# Boost_converter.net
KiCad netlist of a schematic drawn in Altium Designer
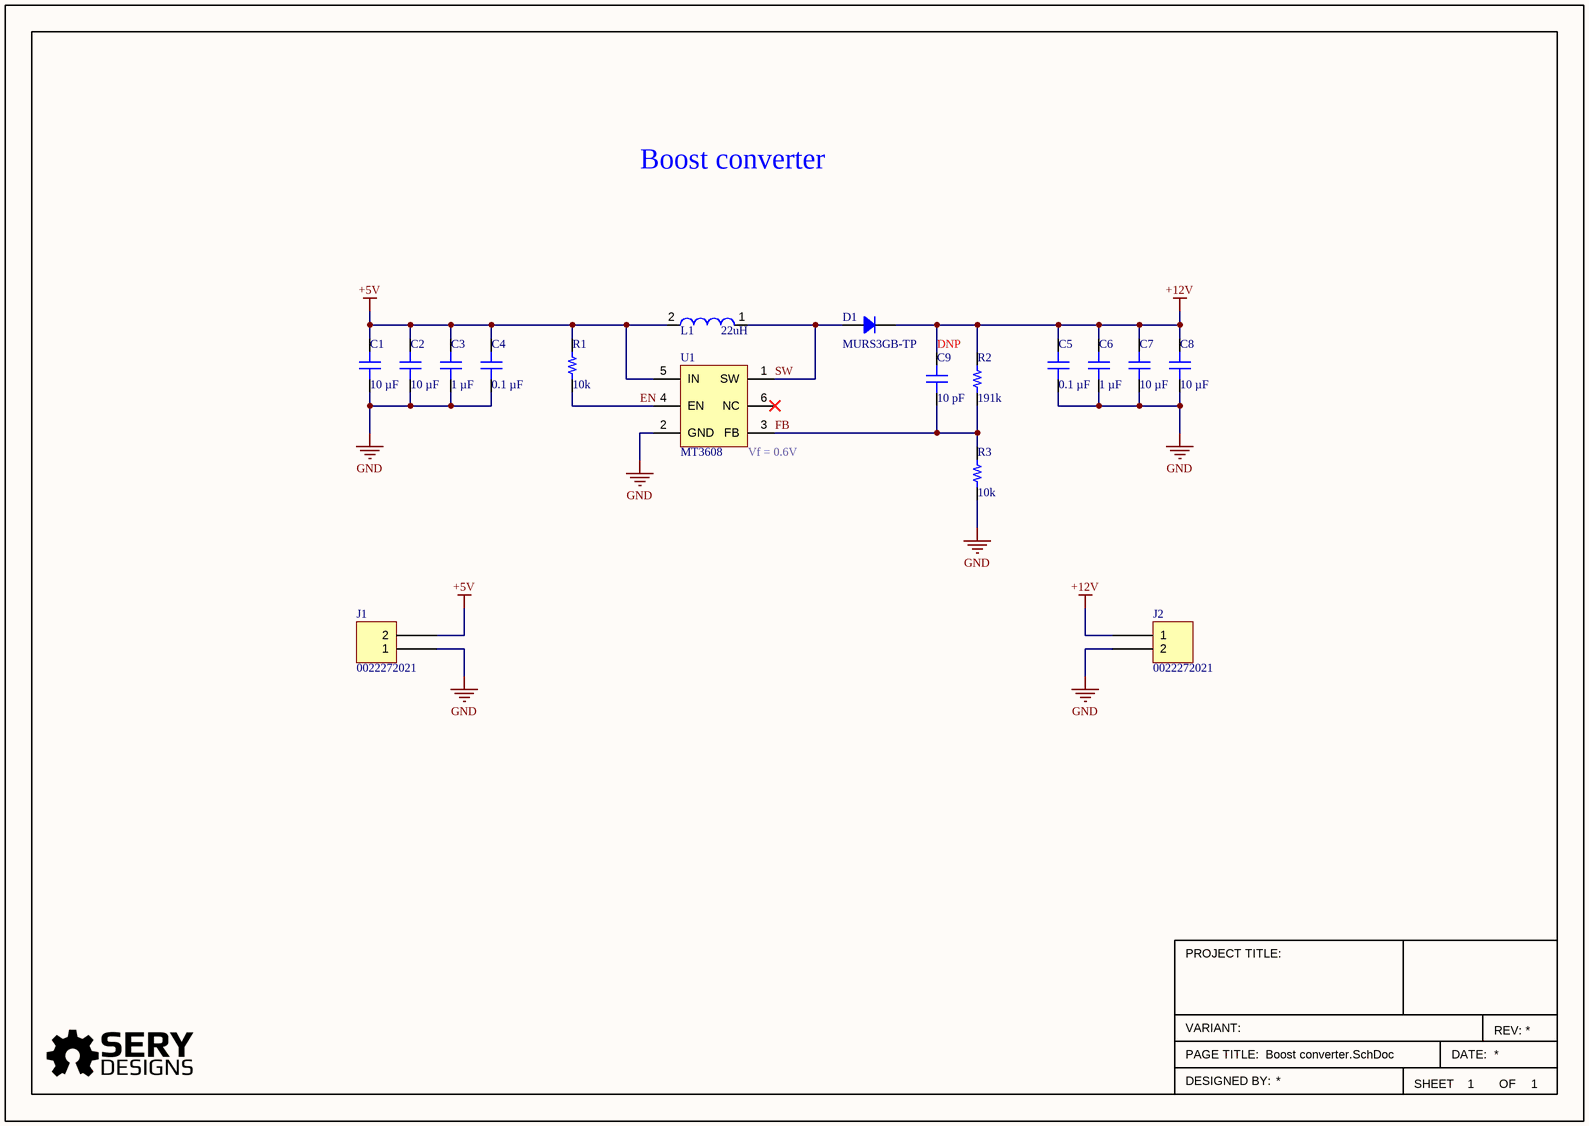
[diagram p0: Boost converter.SchDoc]

(export (version "E")
  (design (tool "Eeschema 10.0.6"))
  (components
    (comp (ref "C1")
      (value "10 µF")
      (footprint "CAP 0805_2012")
      (description "CAP CER 10UF 50V X5R 0805")
      (fields
        (field (name "PART NUMBER") "GRM21BR61H106ME43L")
        (field (name "MANUFACTURER") "Murata Electronics")
      )
      (libsource (lib "Celestial Altium Library - altium_library") (part "Capacitor"))
    )
    (comp (ref "C2")
      (value "10 µF")
      (footprint "CAP 0805_2012")
      (description "CAP CER 10UF 50V X5R 0805")
      (fields
        (field (name "PART NUMBER") "GRM21BR61H106ME43L")
        (field (name "MANUFACTURER") "Murata Electronics")
      )
      (libsource (lib "Celestial Altium Library - altium_library") (part "Capacitor"))
    )
    (comp (ref "C3")
      (value "1 µF")
      (footprint "CAP 0603_1608")
      (description "CAP CER 1UF 50V X7R 0603")
      (fields (field (name "PART NUMBER") "UMK107AB7105KA-T") (field (name "MANUFACTURER") "Taiyo Yuden"))
      (libsource (lib "Celestial Altium Library - altium_library") (part "Capacitor"))
    )
    (comp (ref "C4")
      (value "0.1 µF")
      (footprint "CAP 0402_1005")
      (description "CAP CER 0.1UF 50V X7R 0402")
      (fields
        (field (name "PART NUMBER") "CGA2B3X7R1H104M050BB")
        (field (name "MANUFACTURER") "TDK Corporation")
      )
      (libsource (lib "Celestial Altium Library - altium_library") (part "Capacitor"))
    )
    (comp (ref "C5")
      (value "0.1 µF")
      (footprint "CAP 0402_1005")
      (description "CAP CER 0.1UF 50V X7R 0402")
      (fields
        (field (name "PART NUMBER") "CGA2B3X7R1H104M050BB")
        (field (name "MANUFACTURER") "TDK Corporation")
      )
      (libsource (lib "Celestial Altium Library - altium_library") (part "Capacitor"))
    )
    (comp (ref "C6")
      (value "1 µF")
      (footprint "CAP 0603_1608")
      (description "CAP CER 1UF 50V X7R 0603")
      (fields (field (name "PART NUMBER") "UMK107AB7105KA-T") (field (name "MANUFACTURER") "Taiyo Yuden"))
      (libsource (lib "Celestial Altium Library - altium_library") (part "Capacitor"))
    )
    (comp (ref "C7")
      (value "10 µF")
      (footprint "CAP 0805_2012")
      (description "CAP CER 10UF 50V X5R 0805")
      (fields
        (field (name "PART NUMBER") "GRM21BR61H106ME43L")
        (field (name "MANUFACTURER") "Murata Electronics")
      )
      (libsource (lib "Celestial Altium Library - altium_library") (part "Capacitor"))
    )
    (comp (ref "C8")
      (value "10 µF")
      (footprint "CAP 0805_2012")
      (description "CAP CER 10UF 50V X5R 0805")
      (fields
        (field (name "PART NUMBER") "GRM21BR61H106ME43L")
        (field (name "MANUFACTURER") "Murata Electronics")
      )
      (libsource (lib "Celestial Altium Library - altium_library") (part "Capacitor"))
    )
    (comp (ref "C9")
      (value "10 pF")
      (footprint "CAP 0402_1005")
      (description "CAP CER 10PF 50V C0G/NP0 0402")
      (fields
        (field (name "PART NUMBER") "CL05C100JB5NNNC")
        (field (name "MANUFACTURER") "Samsung Electro-Mechanics")
      )
      (libsource (lib "Celestial Altium Library - altium_library") (part "Capacitor"))
    )
    (comp (ref "D1")
      (value "MURS3GB-TP")
      (footprint "DO214AA SMB")
      (description "3A,400V, SUPER FAST RECOVERY REC")
      (fields (field (name "MANUFACTURER") "Micro Commercial Co"))
      (libsource (lib "Celestial Altium Library - altium_library") (part "Diode"))
    )
    (comp (ref "J1")
      (value "0022272021")
      (footprint "MOLEX KK 0022272021")
      (description "CONN HEADER VERT 2POS 2.54MM")
      (fields (field (name "MANUFACTURER") "Molex"))
      (libsource (lib "") (part "2 Pin_1"))
    )
    (comp (ref "J2")
      (value "0022272021")
      (footprint "MOLEX KK 0022272021")
      (description "CONN HEADER VERT 2POS 2.54MM")
      (fields (field (name "MANUFACTURER") "Molex"))
      (libsource (lib "Celestial Altium Library - altium_library") (part "2 Pin"))
    )
    (comp (ref "L1")
      (value "22uH")
      (footprint "Inductors:NRS8040T220MJGJV")
      (description "Inductor, Fixed, SMD, 22µH, 2.2A")
      (fields (field (name "PART NUMBER") "6006M0220F000") (field (name "MF") "Taiyo Yuden"))
      (libsource (lib "Inductors") (part "NRS8040T220MJGJV"))
    )
    (comp (ref "OSHW-logo1")
      (value "OSHW-logo")
      (footprint "Fabricated:OSHW-logo")
      (description "OSHW logo, no writing")
      (libsource (lib "Fabricated") (part "OSHW-logo"))
    )
    (comp (ref "R1")
      (value "10k")
      (footprint "RES 0402_1005")
      (description "RES SMD 10K OHM 1% 1/16W 0402")
      (fields (field (name "PART NUMBER") "RE0402FRE0710KL") (field (name "MANUFACTURER") "Yageo"))
      (libsource (lib "Celestial Altium Library - altium_library") (part "Resistor"))
    )
    (comp (ref "R2")
      (value "191k")
      (footprint "RES 0402_1005")
      (description "RES SMD 191K OHM 1% 1/16W 0402")
      (fields (field (name "PART NUMBER") "AC0402FR-07191KL") (field (name "MANUFACTURER") "Yageo"))
      (libsource (lib "Celestial Altium Library - altium_library") (part "Resistor"))
    )
    (comp (ref "R3")
      (value "10k")
      (footprint "RES 0402_1005")
      (description "RES SMD 10K OHM 1% 1/16W 0402")
      (fields (field (name "PART NUMBER") "RE0402FRE0710KL") (field (name "MANUFACTURER") "Yageo"))
      (libsource (lib "Celestial Altium Library - altium_library") (part "Resistor"))
    )
    (comp (ref "SeryDesigns-logo1")
      (value "SeryDesigns-logo")
      (footprint "Fabricated:SeryDesigns-logo")
      (description "Sery designs logo")
      (libsource (lib "Fabricated") (part "SeryDesigns-logo"))
    )
    (comp (ref "U1") (value "MT3608") (footprint "ICs:SOT23-6") (libsource (lib "ICs") (part "MT3608")))
  )
  (nets
    (net (code "1") (name "+5V") (class "Default")
      (node (ref "C1") (pin "2") (pinfunction "2_2") (pintype "passive"))
      (node (ref "C2") (pin "2") (pinfunction "2_2") (pintype "passive"))
      (node (ref "C3") (pin "2") (pinfunction "2_2") (pintype "passive"))
      (node (ref "C4") (pin "2") (pinfunction "2_2") (pintype "passive"))
      (node (ref "J1") (pin "2") (pinfunction "2_2") (pintype "passive"))
      (node (ref "L1") (pin "2") (pinfunction "2_2") (pintype "passive"))
      (node (ref "R1") (pin "2") (pinfunction "2_2") (pintype "passive"))
      (node (ref "U1") (pin "5") (pinfunction "IN_5") (pintype "passive"))
    )
    (net (code "2") (name "+12V") (class "Default")
      (node (ref "C5") (pin "2") (pinfunction "2_2") (pintype "passive"))
      (node (ref "C6") (pin "2") (pinfunction "2_2") (pintype "passive"))
      (node (ref "C7") (pin "2") (pinfunction "2_2") (pintype "passive"))
      (node (ref "C8") (pin "2") (pinfunction "2_2") (pintype "passive"))
      (node (ref "C9") (pin "2") (pinfunction "2_2") (pintype "passive"))
      (node (ref "D1") (pin "2") (pinfunction "2_2") (pintype "passive"))
      (node (ref "J2") (pin "1") (pinfunction "1_1") (pintype "passive"))
      (node (ref "R2") (pin "2") (pinfunction "2_2") (pintype "passive"))
    )
    (net (code "3") (name "/EN") (class "Default")
      (node (ref "R1") (pin "1") (pinfunction "1_1") (pintype "passive"))
      (node (ref "U1") (pin "4") (pinfunction "EN_4") (pintype "passive"))
    )
    (net (code "4") (name "/FB") (class "Default")
      (node (ref "C9") (pin "1") (pinfunction "1_1") (pintype "passive"))
      (node (ref "R2") (pin "1") (pinfunction "1_1") (pintype "passive"))
      (node (ref "R3") (pin "2") (pinfunction "2_2") (pintype "passive"))
      (node (ref "U1") (pin "3") (pinfunction "FB_3") (pintype "passive"))
    )
    (net (code "5") (name "/SW") (class "Default")
      (node (ref "D1") (pin "1") (pinfunction "1_1") (pintype "passive"))
      (node (ref "L1") (pin "1") (pinfunction "1_1") (pintype "passive"))
      (node (ref "U1") (pin "1") (pinfunction "SW_1") (pintype "passive"))
    )
    (net (code "6") (name "GND") (class "Default")
      (node (ref "C1") (pin "1") (pinfunction "1_1") (pintype "passive"))
      (node (ref "C2") (pin "1") (pinfunction "1_1") (pintype "passive"))
      (node (ref "C3") (pin "1") (pinfunction "1_1") (pintype "passive"))
      (node (ref "C4") (pin "1") (pinfunction "1_1") (pintype "passive"))
      (node (ref "C5") (pin "1") (pinfunction "1_1") (pintype "passive"))
      (node (ref "C6") (pin "1") (pinfunction "1_1") (pintype "passive"))
      (node (ref "C7") (pin "1") (pinfunction "1_1") (pintype "passive"))
      (node (ref "C8") (pin "1") (pinfunction "1_1") (pintype "passive"))
      (node (ref "J1") (pin "1") (pinfunction "1_1") (pintype "passive"))
      (node (ref "J2") (pin "2") (pinfunction "2_2") (pintype "passive"))
      (node (ref "R3") (pin "1") (pinfunction "1_1") (pintype "passive"))
      (node (ref "U1") (pin "2") (pinfunction "GND_2") (pintype "passive"))
    )
    (net (code "7") (name "unconnected-(U1-NC-Pad6)") (class "Default")
      (node (ref "U1") (pin "6") (pinfunction "NC_6") (pintype "passive+no_connect"))
    )
  )
)
